# hexa2wide.net
KiCad netlist of a schematic drawn in EAGLE
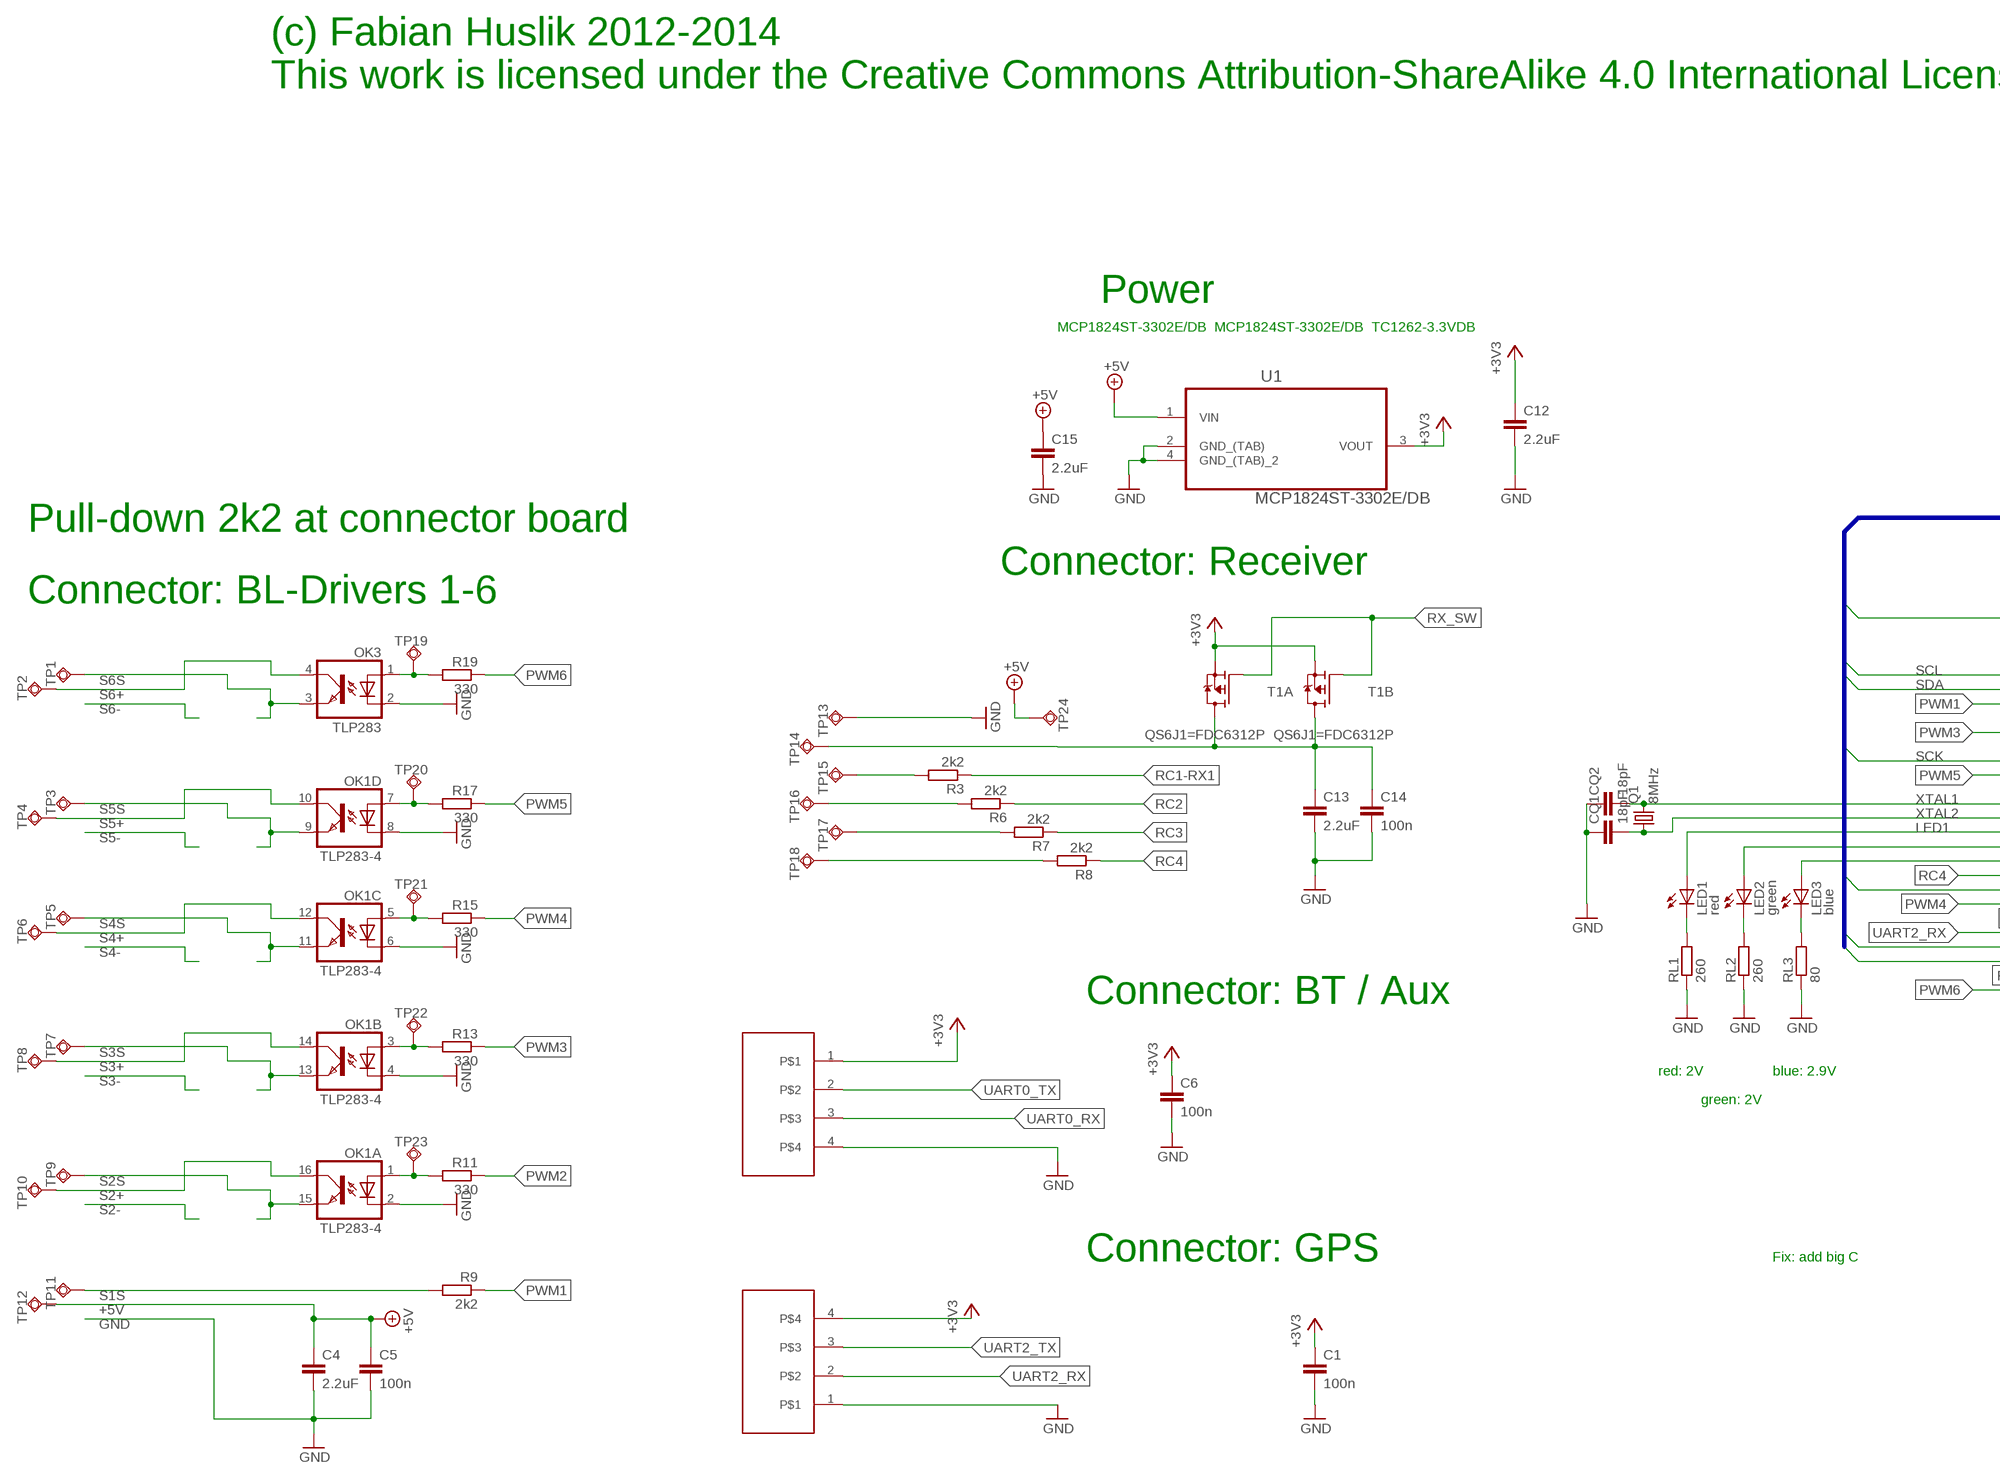
[diagram p0: schematic, sheet 1, part 1 of 2]
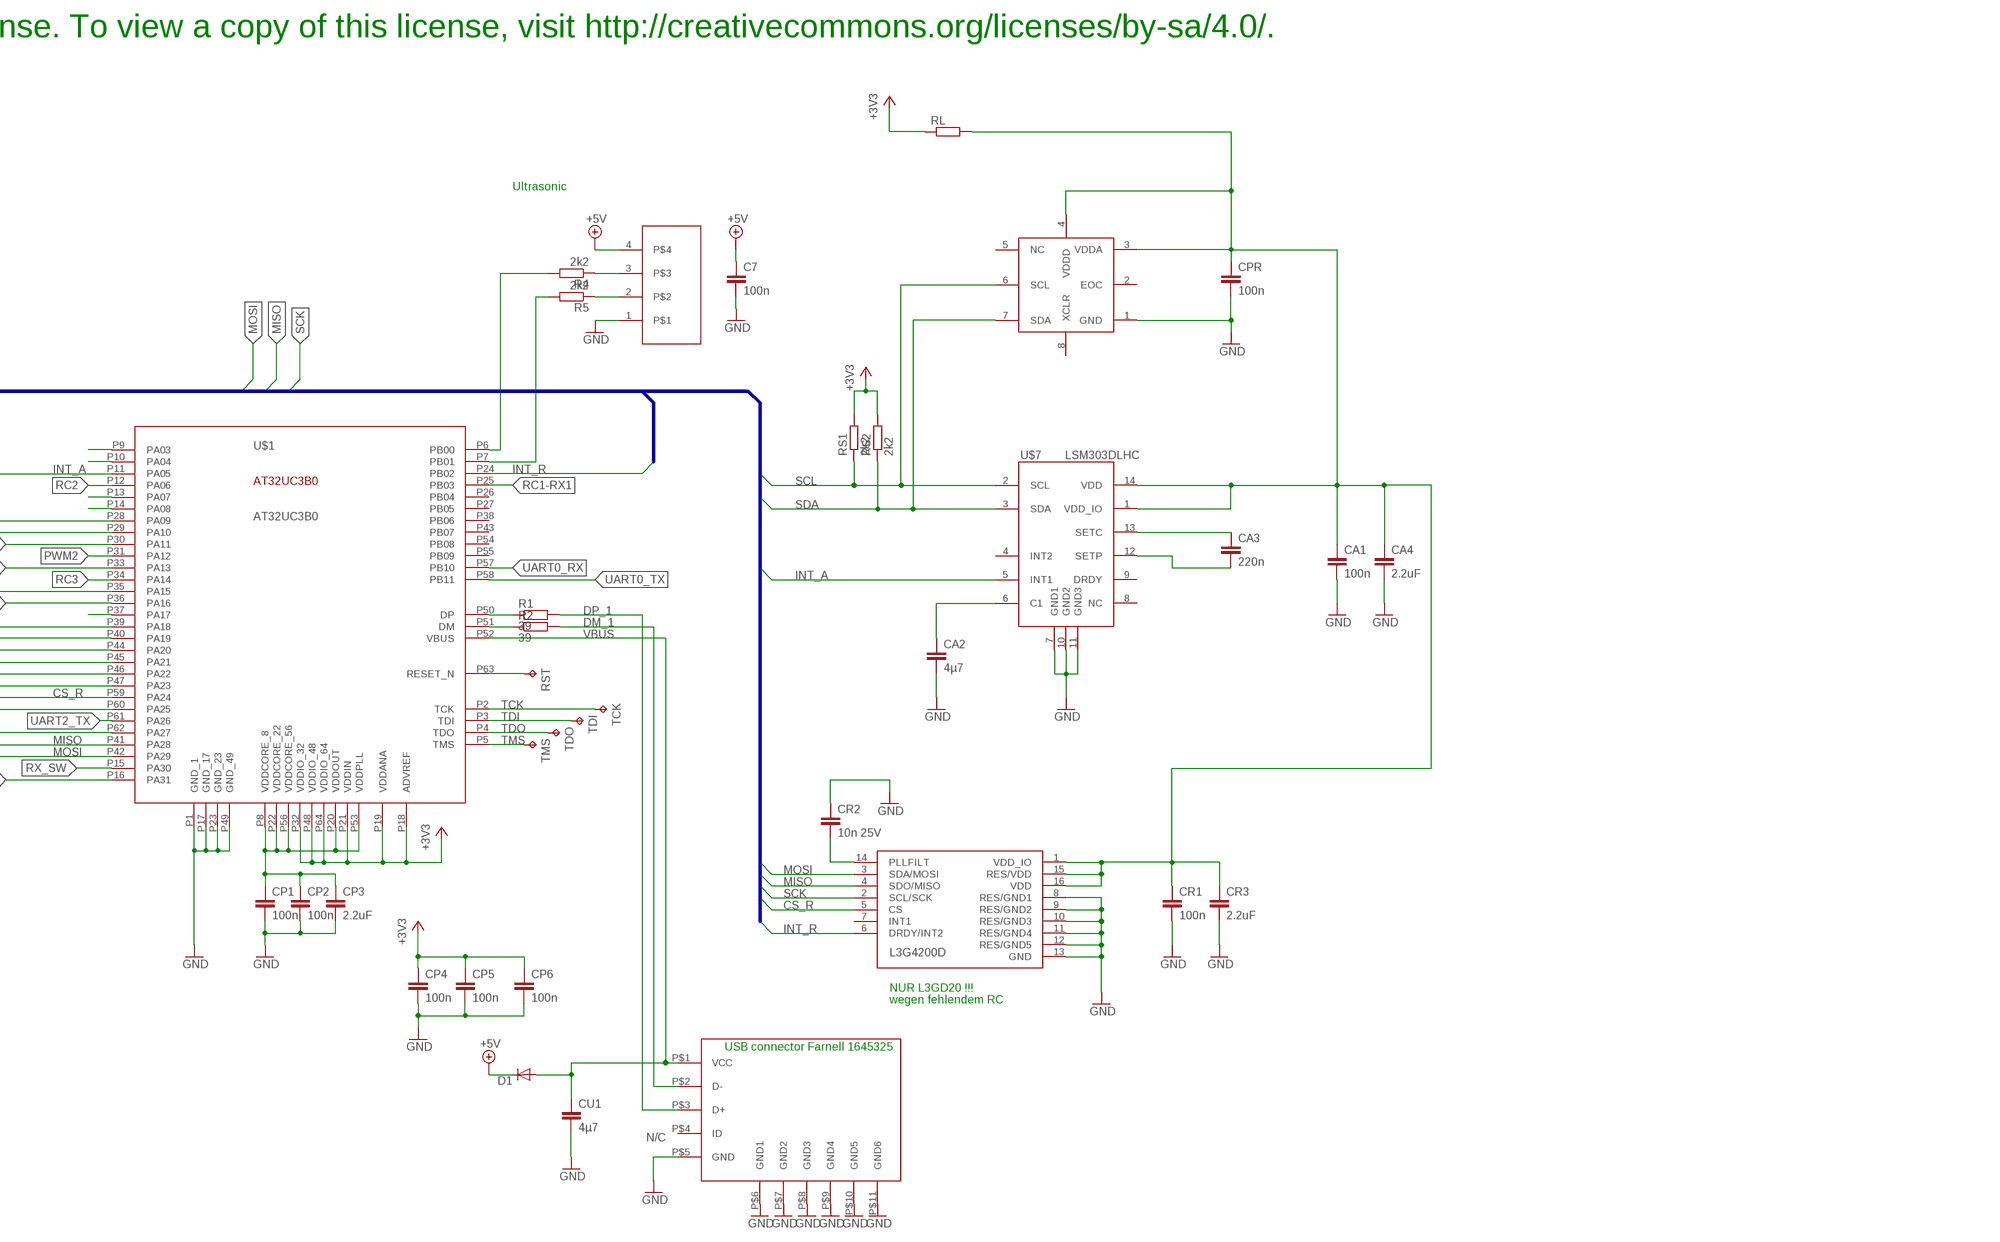
[diagram p1: schematic, sheet 1, part 2 of 2]

(export (version "E")
  (design (tool "Eeschema 10.0.6"))
  (components
    (comp (ref "C1")
      (value "100n")
      (footprint "eagle-import:C0402")
      (fields (field (name "MF") "MULTICOMP") (field (name "MPN") "MCCA000050"))
      (libsource (lib "eagle-import") (part "C-EUC0402"))
    )
    (comp (ref "C4")
      (value "2.2uF")
      (footprint "eagle-import:C0603K")
      (fields (field (name "MF") "MURATA") (field (name "MPN") "GRM188R61C225KE15D"))
      (libsource (lib "eagle-import") (part "C-EUC0603K"))
    )
    (comp (ref "C5")
      (value "100n")
      (footprint "eagle-import:C0402")
      (fields (field (name "MF") "MULTICOMP") (field (name "MPN") "MCCA000050"))
      (libsource (lib "eagle-import") (part "C-EUC0402"))
    )
    (comp (ref "C6")
      (value "100n")
      (footprint "eagle-import:C0402")
      (fields (field (name "MF") "MULTICOMP") (field (name "MPN") "MCCA000050"))
      (libsource (lib "eagle-import") (part "C-EUC0402"))
    )
    (comp (ref "C7")
      (value "100n")
      (footprint "eagle-import:C0402")
      (fields (field (name "MF") "MULTICOMP") (field (name "MPN") "MCCA000050"))
      (libsource (lib "eagle-import") (part "C-EUC0402"))
    )
    (comp (ref "C12")
      (value "2.2uF")
      (footprint "eagle-import:C0603K")
      (fields (field (name "MF") "MURATA") (field (name "MPN") "GRM188R61C225KE15D"))
      (libsource (lib "eagle-import") (part "C-EUC0603K"))
    )
    (comp (ref "C13")
      (value "2.2uF")
      (footprint "eagle-import:C0603K")
      (fields (field (name "MF") "MURATA") (field (name "MPN") "GRM188R61C225KE15D"))
      (libsource (lib "eagle-import") (part "C-EUC0603K"))
    )
    (comp (ref "C14")
      (value "100n")
      (footprint "eagle-import:C0402")
      (fields (field (name "MF") "MULTICOMP") (field (name "MPN") "MCCA000050"))
      (libsource (lib "eagle-import") (part "C-EUC0402"))
    )
    (comp (ref "C15")
      (value "2.2uF")
      (footprint "eagle-import:C0603K")
      (fields (field (name "MF") "MURATA") (field (name "MPN") "GRM188R61C225KE15D"))
      (libsource (lib "eagle-import") (part "C-EUC0603K"))
    )
    (comp (ref "CA1")
      (value "100n")
      (footprint "eagle-import:C0402")
      (fields (field (name "MF") "MULTICOMP") (field (name "MPN") "MCCA000050"))
      (libsource (lib "eagle-import") (part "C-EUC0402"))
    )
    (comp (ref "CA2")
      (value "4µ7")
      (footprint "eagle-import:C0805")
      (fields (field (name "MF") "MURATA") (field (name "MPN") "GRM219R61C475KE15D"))
      (libsource (lib "eagle-import") (part "C-EUC0805"))
    )
    (comp (ref "CA3")
      (value "220n")
      (footprint "eagle-import:C0402")
      (fields (field (name "MF") "KEMET") (field (name "MPN") "C0402C224K9PACTU"))
      (libsource (lib "eagle-import") (part "C-EUC0402"))
    )
    (comp (ref "CA4")
      (value "2.2uF")
      (footprint "eagle-import:C0603K")
      (fields (field (name "MF") "MURATA") (field (name "MPN") "GRM188R61C225KE15D"))
      (libsource (lib "eagle-import") (part "C-EUC0603K"))
    )
    (comp (ref "CP1")
      (value "100n")
      (footprint "eagle-import:C0402")
      (fields (field (name "MF") "MULTICOMP") (field (name "MPN") "MCCA000050"))
      (libsource (lib "eagle-import") (part "C-EUC0402"))
    )
    (comp (ref "CP2")
      (value "100n")
      (footprint "eagle-import:C0402")
      (fields (field (name "MF") "MULTICOMP") (field (name "MPN") "MCCA000050"))
      (libsource (lib "eagle-import") (part "C-EUC0402"))
    )
    (comp (ref "CP3")
      (value "2.2uF")
      (footprint "eagle-import:C0603K")
      (fields (field (name "MF") "MURATA") (field (name "MPN") "GRM188R61C225KE15D"))
      (libsource (lib "eagle-import") (part "C-EUC0603K"))
    )
    (comp (ref "CP4")
      (value "100n")
      (footprint "eagle-import:C0402")
      (fields (field (name "MF") "MULTICOMP") (field (name "MPN") "MCCA000050"))
      (libsource (lib "eagle-import") (part "C-EUC0402"))
    )
    (comp (ref "CP5")
      (value "100n")
      (footprint "eagle-import:C0402")
      (fields (field (name "MF") "MULTICOMP") (field (name "MPN") "MCCA000050"))
      (libsource (lib "eagle-import") (part "C-EUC0402"))
    )
    (comp (ref "CP6")
      (value "100n")
      (footprint "eagle-import:C0402")
      (fields (field (name "MF") "MULTICOMP") (field (name "MPN") "MCCA000050"))
      (libsource (lib "eagle-import") (part "C-EUC0402"))
    )
    (comp (ref "CPR")
      (value "100n")
      (footprint "eagle-import:C0402")
      (fields (field (name "MF") "MULTICOMP") (field (name "MPN") "MCCA000050"))
      (libsource (lib "eagle-import") (part "C-EUC0402"))
    )
    (comp (ref "CQ1")
      (value "18pF")
      (footprint "eagle-import:C0402")
      (fields (field (name "MF") "KEMET") (field (name "MPN") "C0402C180J5GACTU"))
      (libsource (lib "eagle-import") (part "C-EUC0402"))
    )
    (comp (ref "CQ2")
      (value "18pF")
      (footprint "eagle-import:C0402")
      (fields (field (name "MF") "KEMET") (field (name "MPN") "C0402C180J5GACTU"))
      (libsource (lib "eagle-import") (part "C-EUC0402"))
    )
    (comp (ref "CR1")
      (value "100n")
      (footprint "eagle-import:C0402")
      (fields (field (name "MF") "MULTICOMP") (field (name "MPN") "MCCA000050"))
      (libsource (lib "eagle-import") (part "C-EUC0402"))
    )
    (comp (ref "CR2")
      (value "10n 25V")
      (footprint "eagle-import:C0402")
      (fields (field (name "MF") "MULTICOMP") (field (name "MPN") "MCCA000076"))
      (libsource (lib "eagle-import") (part "C-EUC0402"))
    )
    (comp (ref "CR3")
      (value "2.2uF")
      (footprint "eagle-import:C0603K")
      (fields (field (name "MF") "MURATA") (field (name "MPN") "GRM188R61C225KE15D"))
      (libsource (lib "eagle-import") (part "C-EUC0603K"))
    )
    (comp (ref "CU1")
      (value "4µ7")
      (footprint "eagle-import:C0805")
      (fields (field (name "MF") "MURATA") (field (name "MPN") "GRM219R61C475KE15D"))
      (libsource (lib "eagle-import") (part "C-EUC0805"))
    )
    (comp (ref "D1")
      (value "DIODE-MICROMELF-R")
      (footprint "eagle-import:MICROMELF-R")
      (libsource (lib "eagle-import") (part "DIODE-MICROMELF-R"))
    )
    (comp (ref "LED1")
      (value "red")
      (footprint "eagle-import:CHIP-LED0603")
      (fields (field (name "MF") "AVAGO TECHNOLOGIES") (field (name "MPN") "ASMT-RR45-AQ902"))
      (libsource (lib "eagle-import") (part "LEDCHIP-LED0603"))
    )
    (comp (ref "LED2")
      (value "green")
      (footprint "eagle-import:CHIP-LED0603")
      (fields (field (name "MF") "AVAGO TECHNOLOGIES") (field (name "MPN") "ASMT-RF45-AN002"))
      (libsource (lib "eagle-import") (part "LEDCHIP-LED0603"))
    )
    (comp (ref "LED3")
      (value "blue")
      (footprint "eagle-import:CHIP-LED0603")
      (fields (field (name "MF") "ROHM") (field (name "MPN") "SMLE12BC7TT86Q"))
      (libsource (lib "eagle-import") (part "LEDCHIP-LED0603"))
    )
    (comp (ref "OK1")
      (value "TLP283-4")
      (footprint "eagle-import:MINI-FLAT-16")
      (fields
        (field (name "MF") "AVAGO TECHNOLOGIES")
        (field (name "MPN") "ACPL-247-500E")
        (field (name "OC_FARNELL") "1634758")
      )
      (libsource (lib "eagle-import") (part "TLP283-4"))
    )
    (comp (ref "OK3")
      (value "TLP283")
      (footprint "eagle-import:MINI-FLAT-4")
      (fields
        (field (name "MF") "AVAGO TECHNOLOGIES")
        (field (name "MPN") "ACPL-217-500E")
        (field (name "OC_FARNELL") "1602614")
      )
      (libsource (lib "eagle-import") (part "TLP283"))
    )
    (comp (ref "Q1")
      (value "8MHz")
      (footprint "eagle-import:CTS406")
      (fields
        (field (name "MF") "ABRACON")
        (field (name "MPN") "ABMM2-8.000MHZ-E2-T")
        (field (name "OC_FARNELL") "1611803")
      )
      (libsource (lib "eagle-import") (part "CRYSTALCTS406"))
    )
    (comp (ref "R1")
      (value "39")
      (footprint "eagle-import:R0402")
      (fields (field (name "MF") "VISHAY DRALORIC") (field (name "MPN") "CRCW040239R0FKEAHP"))
      (libsource (lib "eagle-import") (part "R-EU_R0402"))
    )
    (comp (ref "R2")
      (value "39")
      (footprint "eagle-import:R0402")
      (fields (field (name "MF") "VISHAY DRALORIC") (field (name "MPN") "CRCW040239R0FKEAHP"))
      (libsource (lib "eagle-import") (part "R-EU_R0402"))
    )
    (comp (ref "R3")
      (value "2k2")
      (footprint "eagle-import:R0402")
      (fields (field (name "MF") "VISHAY DRALORIC") (field (name "MPN") "CRCW040210K5FKED"))
      (libsource (lib "eagle-import") (part "R-EU_R0402"))
    )
    (comp (ref "R4")
      (value "2k2")
      (footprint "eagle-import:R0402")
      (fields (field (name "MF") "VISHAY DRALORIC") (field (name "MPN") "CRCW040210K5FKED"))
      (libsource (lib "eagle-import") (part "R-EU_R0402"))
    )
    (comp (ref "R5")
      (value "2k2")
      (footprint "eagle-import:R0402")
      (fields (field (name "MF") "VISHAY DRALORIC") (field (name "MPN") "CRCW040210K5FKED"))
      (libsource (lib "eagle-import") (part "R-EU_R0402"))
    )
    (comp (ref "R6")
      (value "2k2")
      (footprint "eagle-import:R0402")
      (fields (field (name "MF") "VISHAY DRALORIC") (field (name "MPN") "CRCW040210K5FKED"))
      (libsource (lib "eagle-import") (part "R-EU_R0402"))
    )
    (comp (ref "R7")
      (value "2k2")
      (footprint "eagle-import:R0402")
      (fields (field (name "MF") "VISHAY DRALORIC") (field (name "MPN") "CRCW040210K5FKED"))
      (libsource (lib "eagle-import") (part "R-EU_R0402"))
    )
    (comp (ref "R8")
      (value "2k2")
      (footprint "eagle-import:R0402")
      (fields (field (name "MF") "VISHAY DRALORIC") (field (name "MPN") "CRCW040210K5FKED"))
      (libsource (lib "eagle-import") (part "R-EU_R0402"))
    )
    (comp (ref "R9")
      (value "2k2")
      (footprint "eagle-import:R0402")
      (fields (field (name "MF") "VISHAY DRALORIC") (field (name "MPN") "CRCW040210K5FKED"))
      (libsource (lib "eagle-import") (part "R-EU_R0402"))
    )
    (comp (ref "R11")
      (value "330")
      (footprint "eagle-import:R0402")
      (fields (field (name "MF") "MULTICOMP") (field (name "MPN") "MCMR04X331 JTL"))
      (libsource (lib "eagle-import") (part "R-EU_R0402"))
    )
    (comp (ref "R13")
      (value "330")
      (footprint "eagle-import:R0402")
      (fields (field (name "MF") "MULTICOMP") (field (name "MPN") "MCMR04X331 JTL"))
      (libsource (lib "eagle-import") (part "R-EU_R0402"))
    )
    (comp (ref "R15")
      (value "330")
      (footprint "eagle-import:R0402")
      (fields (field (name "MF") "MULTICOMP") (field (name "MPN") "MCMR04X331 JTL"))
      (libsource (lib "eagle-import") (part "R-EU_R0402"))
    )
    (comp (ref "R17")
      (value "330")
      (footprint "eagle-import:R0402")
      (fields (field (name "MF") "MULTICOMP") (field (name "MPN") "MCMR04X331 JTL"))
      (libsource (lib "eagle-import") (part "R-EU_R0402"))
    )
    (comp (ref "R19")
      (value "330")
      (footprint "eagle-import:R0402")
      (fields (field (name "MF") "MULTICOMP") (field (name "MPN") "MCMR04X331 JTL"))
      (libsource (lib "eagle-import") (part "R-EU_R0402"))
    )
    (comp (ref "RL")
      (value "R-EU_R0603")
      (footprint "eagle-import:R0603")
      (fields (field (name "MF") "WURTH ELEKTRONIK") (field (name "MPN") "74279266"))
      (libsource (lib "eagle-import") (part "R-EU_R0603"))
    )
    (comp (ref "RL1")
      (value "260")
      (footprint "eagle-import:R0402")
      (fields (field (name "MF") "VISHAY DRALORIC") (field (name "MPN") "CRCW0402604RFKED"))
      (libsource (lib "eagle-import") (part "R-EU_R0402"))
    )
    (comp (ref "RL2")
      (value "260")
      (footprint "eagle-import:R0402")
      (fields (field (name "MF") "VISHAY DRALORIC") (field (name "MPN") "CRCW0402604RFKED"))
      (libsource (lib "eagle-import") (part "R-EU_R0402"))
    )
    (comp (ref "RL3")
      (value "80")
      (footprint "eagle-import:R0402")
      (fields (field (name "MF") "PANASONIC") (field (name "MPN") "ERJ2RKF8062X"))
      (libsource (lib "eagle-import") (part "R-EU_R0402"))
    )
    (comp (ref "RS1")
      (value "2k2")
      (footprint "eagle-import:R0402")
      (fields (field (name "MF") "VISHAY DRALORIC") (field (name "MPN") "CRCW040210K5FKED"))
      (libsource (lib "eagle-import") (part "R-EU_R0402"))
    )
    (comp (ref "RS2")
      (value "2k2")
      (footprint "eagle-import:R0402")
      (fields (field (name "MF") "VISHAY DRALORIC") (field (name "MPN") "CRCW040210K5FKED"))
      (libsource (lib "eagle-import") (part "R-EU_R0402"))
    )
    (comp (ref "RST")
      (value "TPB1,27")
      (footprint "eagle-import:B1,27")
      (libsource (lib "eagle-import") (part "TPB1,27"))
    )
    (comp (ref "T1")
      (value "QS6J1=FDC6312P")
      (footprint "eagle-import:SUPERSOT-6")
      (fields
        (field (name "MF") "FAIRCHILD SEMICONDUCTOR")
        (field (name "MPN") "FDC6312P")
        (field (name "OC_FARNELL") "1700713")
      )
      (libsource (lib "eagle-import") (part "QS6J1=FDC6312P"))
    )
    (comp (ref "TCK")
      (value "TPB1,27")
      (footprint "eagle-import:B1,27")
      (libsource (lib "eagle-import") (part "TPB1,27"))
    )
    (comp (ref "TDI")
      (value "TPB1,27")
      (footprint "eagle-import:B1,27")
      (libsource (lib "eagle-import") (part "TPB1,27"))
    )
    (comp (ref "TDO")
      (value "TPB1,27")
      (footprint "eagle-import:B1,27")
      (libsource (lib "eagle-import") (part "TPB1,27"))
    )
    (comp (ref "TMS")
      (value "TPB1,27")
      (footprint "eagle-import:B1,27")
      (libsource (lib "eagle-import") (part "TPB1,27"))
    )
    (comp (ref "TP1")
      (value "TPSQTP16SQ")
      (footprint "eagle-import:TP16SQ")
      (libsource (lib "eagle-import") (part "TPSQTP16SQ"))
    )
    (comp (ref "TP2")
      (value "TPSQTP16SQ")
      (footprint "eagle-import:TP16SQ")
      (libsource (lib "eagle-import") (part "TPSQTP16SQ"))
    )
    (comp (ref "TP3")
      (value "TPSQTP16SQ")
      (footprint "eagle-import:TP16SQ")
      (libsource (lib "eagle-import") (part "TPSQTP16SQ"))
    )
    (comp (ref "TP4")
      (value "TPSQTP16SQ")
      (footprint "eagle-import:TP16SQ")
      (libsource (lib "eagle-import") (part "TPSQTP16SQ"))
    )
    (comp (ref "TP5")
      (value "TPSQTP16SQ")
      (footprint "eagle-import:TP16SQ")
      (libsource (lib "eagle-import") (part "TPSQTP16SQ"))
    )
    (comp (ref "TP6")
      (value "TPSQTP16SQ")
      (footprint "eagle-import:TP16SQ")
      (libsource (lib "eagle-import") (part "TPSQTP16SQ"))
    )
    (comp (ref "TP7")
      (value "TPSQTP16SQ")
      (footprint "eagle-import:TP16SQ")
      (libsource (lib "eagle-import") (part "TPSQTP16SQ"))
    )
    (comp (ref "TP8")
      (value "TPSQTP16SQ")
      (footprint "eagle-import:TP16SQ")
      (libsource (lib "eagle-import") (part "TPSQTP16SQ"))
    )
    (comp (ref "TP9")
      (value "TPSQTP16SQ")
      (footprint "eagle-import:TP16SQ")
      (libsource (lib "eagle-import") (part "TPSQTP16SQ"))
    )
    (comp (ref "TP10")
      (value "TPSQTP16SQ")
      (footprint "eagle-import:TP16SQ")
      (libsource (lib "eagle-import") (part "TPSQTP16SQ"))
    )
    (comp (ref "TP11")
      (value "TPSQTP16SQ")
      (footprint "eagle-import:TP16SQ")
      (libsource (lib "eagle-import") (part "TPSQTP16SQ"))
    )
    (comp (ref "TP12")
      (value "TPSQTP16SQ")
      (footprint "eagle-import:TP16SQ")
      (libsource (lib "eagle-import") (part "TPSQTP16SQ"))
    )
    (comp (ref "TP13")
      (value "TPSQTP16SQ")
      (footprint "eagle-import:TP16SQ")
      (libsource (lib "eagle-import") (part "TPSQTP16SQ"))
    )
    (comp (ref "TP14")
      (value "TPSQTP16SQ")
      (footprint "eagle-import:TP16SQ")
      (libsource (lib "eagle-import") (part "TPSQTP16SQ"))
    )
    (comp (ref "TP15")
      (value "TPSQTP16SQ")
      (footprint "eagle-import:TP16SQ")
      (libsource (lib "eagle-import") (part "TPSQTP16SQ"))
    )
    (comp (ref "TP16")
      (value "TPSQTP16SQ")
      (footprint "eagle-import:TP16SQ")
      (libsource (lib "eagle-import") (part "TPSQTP16SQ"))
    )
    (comp (ref "TP17")
      (value "TPSQTP16SQ")
      (footprint "eagle-import:TP16SQ")
      (libsource (lib "eagle-import") (part "TPSQTP16SQ"))
    )
    (comp (ref "TP18")
      (value "TPSQTP16SQ")
      (footprint "eagle-import:TP16SQ")
      (libsource (lib "eagle-import") (part "TPSQTP16SQ"))
    )
    (comp (ref "TP19")
      (value "TPSQTP10SQ")
      (footprint "eagle-import:TP10SQ")
      (libsource (lib "eagle-import") (part "TPSQTP10SQ"))
    )
    (comp (ref "TP20")
      (value "TPSQTP10SQ")
      (footprint "eagle-import:TP10SQ")
      (libsource (lib "eagle-import") (part "TPSQTP10SQ"))
    )
    (comp (ref "TP21")
      (value "TPSQTP10SQ")
      (footprint "eagle-import:TP10SQ")
      (libsource (lib "eagle-import") (part "TPSQTP10SQ"))
    )
    (comp (ref "TP22")
      (value "TPSQTP10SQ")
      (footprint "eagle-import:TP10SQ")
      (libsource (lib "eagle-import") (part "TPSQTP10SQ"))
    )
    (comp (ref "TP23")
      (value "TPSQTP10SQ")
      (footprint "eagle-import:TP10SQ")
      (libsource (lib "eagle-import") (part "TPSQTP10SQ"))
    )
    (comp (ref "TP24")
      (value "TPSQTP10SQ")
      (footprint "eagle-import:TP10SQ")
      (libsource (lib "eagle-import") (part "TPSQTP10SQ"))
    )
    (comp (ref "U$1")
      (value "AT32UC3B0")
      (footprint "eagle-import:JEDEC_MS-026")
      (fields (field (name "MF") "ATMEL") (field (name "MPN") "AT32UC3B0256-A2UT"))
      (libsource (lib "eagle-import") (part "AT32UC3B0"))
    )
    (comp (ref "U$4")
      (value "UBB_MICRO_HIROSE")
      (footprint "eagle-import:USB_MICRO")
      (fields (field (name "MF") "HRS (HIROSE)") (field (name "MPN") "ZX62-B-5PA(11)"))
      (libsource (lib "eagle-import") (part "UBB_MICRO_HIROSE"))
    )
    (comp (ref "U$5")
      (value "L3G4200DHAND")
      (footprint "eagle-import:LGA16_HAND")
      (fields (field (name "MF") "STMICROELECTRONICS") (field (name "MPN") "L3GD20"))
      (libsource (lib "eagle-import") (part "L3G4200DHAND"))
    )
    (comp (ref "U$7")
      (value "LSM303HAND")
      (footprint "eagle-import:LGA14_HAND")
      (fields (field (name "MF") "STMICROELECTRONICS") (field (name "MPN") "LSM303DLHC"))
      (libsource (lib "eagle-import") (part "LSM303HAND"))
    )
    (comp (ref "U$9")
      (value "BMP085")
      (footprint "eagle-import:BMP085")
      (libsource (lib "eagle-import") (part "BMP085"))
    )
    (comp (ref "U$10")
      (value "4WIRE_CONN")
      (footprint "eagle-import:4WIRE_PIN")
      (libsource (lib "eagle-import") (part "4WIRE_CONN"))
    )
    (comp (ref "U$11")
      (value "4WIRE_CONN")
      (footprint "eagle-import:4WIRE_PIN")
      (libsource (lib "eagle-import") (part "4WIRE_CONN"))
    )
    (comp (ref "U$12")
      (value "4WIRE_CONN")
      (footprint "eagle-import:4WIRE_PIN")
      (libsource (lib "eagle-import") (part "4WIRE_CONN"))
    )
    (comp (ref "U1")
      (value "MCP1824ST-3302E/DB")
      (footprint "eagle-import:SOT230P700X180-4N")
      (fields
        (field (name "MF") "MICROCHIP")
        (field (name "MPN") "MCP1824ST-3302E/DB")
        (field (name "OC_FARNELL") "1578379")
      )
      (libsource (lib "eagle-import") (part "MCP1824ST-3302E/DB"))
    )
  )
  (nets
    (net (code "1") (name "+3V3") (class "Default")
      (node (ref "C1") (pin "1") (pinfunction "1_1") (pintype "passive"))
      (node (ref "C12") (pin "1") (pinfunction "1_1") (pintype "passive"))
      (node (ref "C6") (pin "1") (pinfunction "1_1") (pintype "passive"))
      (node (ref "CP4") (pin "1") (pinfunction "1_1") (pintype "passive"))
      (node (ref "CP5") (pin "1") (pinfunction "1_1") (pintype "passive"))
      (node (ref "CP6") (pin "1") (pinfunction "1_1") (pintype "passive"))
      (node (ref "RL") (pin "1") (pinfunction "1_1") (pintype "passive"))
      (node (ref "RS1") (pin "2") (pinfunction "2_2") (pintype "passive"))
      (node (ref "RS2") (pin "2") (pinfunction "2_2") (pintype "passive"))
      (node (ref "T1") (pin "P$2") (pinfunction "S_P$2") (pintype "passive"))
      (node (ref "T1") (pin "P$5") (pinfunction "S_P$5") (pintype "passive"))
      (node (ref "U$1") (pin "P18") (pinfunction "ADVREF_P18") (pintype "power_in"))
      (node (ref "U$1") (pin "P19") (pinfunction "VDDANA_P19") (pintype "power_in"))
      (node (ref "U$1") (pin "P21") (pinfunction "VDDIN_P21") (pintype "power_in"))
      (node (ref "U$1") (pin "P32") (pinfunction "VDDIO_32_P32") (pintype "power_in"))
      (node (ref "U$1") (pin "P48") (pinfunction "VDDIO_48_P48") (pintype "power_in"))
      (node (ref "U$1") (pin "P64") (pinfunction "VDDIO_64_P64") (pintype "power_in"))
      (node (ref "U$10") (pin "4") (pinfunction "P$4_4") (pintype "bidirectional"))
      (node (ref "U$11") (pin "1") (pinfunction "P$1_1") (pintype "bidirectional"))
      (node (ref "U1") (pin "3") (pinfunction "VOUT_3") (pintype "output"))
    )
    (net (code "2") (name "+5V") (class "Default")
      (node (ref "C15") (pin "1") (pinfunction "1_1") (pintype "passive"))
      (node (ref "C4") (pin "1") (pinfunction "1_1") (pintype "passive"))
      (node (ref "C5") (pin "1") (pinfunction "1_1") (pintype "passive"))
      (node (ref "C7") (pin "1") (pinfunction "1_1") (pintype "passive"))
      (node (ref "D1") (pin "C") (pinfunction "C_C") (pintype "passive"))
      (node (ref "TP12") (pin "TP") (pinfunction "TP_TP") (pintype "input"))
      (node (ref "TP24") (pin "TP") (pinfunction "TP_TP") (pintype "input"))
      (node (ref "U$12") (pin "4") (pinfunction "P$4_4") (pintype "bidirectional"))
      (node (ref "U1") (pin "1") (pinfunction "VIN_1") (pintype "input"))
    )
    (net (code "3") (name "/CS_R") (class "Default")
      (node (ref "U$1") (pin "P59") (pinfunction "PA24_P59") (pintype "bidirectional"))
      (node (ref "U$5") (pin "5") (pinfunction "CS_5") (pintype "input"))
    )
    (net (code "4") (name "/DM_1") (class "Default")
      (node (ref "R2") (pin "2") (pinfunction "2_2") (pintype "passive"))
      (node (ref "U$4") (pin "P$2") (pinfunction "D-_P$2") (pintype "bidirectional"))
    )
    (net (code "5") (name "/DP_1") (class "Default")
      (node (ref "R1") (pin "2") (pinfunction "2_2") (pintype "passive"))
      (node (ref "U$4") (pin "P$3") (pinfunction "D+_P$3") (pintype "bidirectional"))
    )
    (net (code "6") (name "/INT_A") (class "Default")
      (node (ref "U$1") (pin "P11") (pinfunction "PA05_P11") (pintype "bidirectional"))
      (node (ref "U$7") (pin "5") (pinfunction "INT1_5") (pintype "bidirectional"))
    )
    (net (code "7") (name "/INT_R") (class "Default")
      (node (ref "U$1") (pin "P24") (pinfunction "PB02_P24") (pintype "bidirectional"))
      (node (ref "U$5") (pin "6") (pinfunction "DRDY/INT2_6") (pintype "output"))
    )
    (net (code "8") (name "/LED1") (class "Default")
      (node (ref "LED1") (pin "A") (pinfunction "A_A") (pintype "passive"))
      (node (ref "U$1") (pin "P44") (pinfunction "PA20_P44") (pintype "bidirectional"))
    )
    (net (code "9") (name "/S1S") (class "Default")
      (node (ref "R9") (pin "2") (pinfunction "2_2") (pintype "passive"))
      (node (ref "TP11") (pin "TP") (pinfunction "TP_TP") (pintype "input"))
    )
    (net (code "10") (name "/S2+") (class "Default")
      (node (ref "OK1") (pin "16") (pinfunction "COL_16") (pintype "passive"))
      (node (ref "TP10") (pin "TP") (pinfunction "TP_TP") (pintype "input"))
    )
    (net (code "12") (name "/S2S") (class "Default")
      (node (ref "OK1") (pin "15") (pinfunction "EMIT_15") (pintype "passive"))
      (node (ref "TP9") (pin "TP") (pinfunction "TP_TP") (pintype "input"))
    )
    (net (code "13") (name "/S3+") (class "Default")
      (node (ref "OK1") (pin "14") (pinfunction "COL_14") (pintype "passive"))
      (node (ref "TP8") (pin "TP") (pinfunction "TP_TP") (pintype "input"))
    )
    (net (code "15") (name "/S3S") (class "Default")
      (node (ref "OK1") (pin "13") (pinfunction "EMIT_13") (pintype "passive"))
      (node (ref "TP7") (pin "TP") (pinfunction "TP_TP") (pintype "input"))
    )
    (net (code "16") (name "/S4+") (class "Default")
      (node (ref "OK1") (pin "12") (pinfunction "COL_12") (pintype "passive"))
      (node (ref "TP6") (pin "TP") (pinfunction "TP_TP") (pintype "input"))
    )
    (net (code "18") (name "/S4S") (class "Default")
      (node (ref "OK1") (pin "11") (pinfunction "EMIT_11") (pintype "passive"))
      (node (ref "TP5") (pin "TP") (pinfunction "TP_TP") (pintype "input"))
    )
    (net (code "19") (name "/S5+") (class "Default")
      (node (ref "OK1") (pin "10") (pinfunction "COL_10") (pintype "passive"))
      (node (ref "TP4") (pin "TP") (pinfunction "TP_TP") (pintype "input"))
    )
    (net (code "21") (name "/S5S") (class "Default")
      (node (ref "OK1") (pin "9") (pinfunction "EMIT_9") (pintype "passive"))
      (node (ref "TP3") (pin "TP") (pinfunction "TP_TP") (pintype "input"))
    )
    (net (code "22") (name "/S6+") (class "Default")
      (node (ref "OK3") (pin "4") (pinfunction "COL_4") (pintype "passive"))
      (node (ref "TP2") (pin "TP") (pinfunction "TP_TP") (pintype "input"))
    )
    (net (code "24") (name "/S6S") (class "Default")
      (node (ref "OK3") (pin "3") (pinfunction "EMIT_3") (pintype "passive"))
      (node (ref "TP1") (pin "TP") (pinfunction "TP_TP") (pintype "input"))
    )
    (net (code "25") (name "/SCL") (class "Default")
      (node (ref "RS1") (pin "1") (pinfunction "1_1") (pintype "passive"))
      (node (ref "U$1") (pin "P28") (pinfunction "PA09_P28") (pintype "bidirectional"))
      (node (ref "U$7") (pin "2") (pinfunction "SCL_2") (pintype "bidirectional"))
      (node (ref "U$9") (pin "6") (pinfunction "SCL_6") (pintype "bidirectional"))
    )
    (net (code "26") (name "/SDA") (class "Default")
      (node (ref "RS2") (pin "1") (pinfunction "1_1") (pintype "passive"))
      (node (ref "U$1") (pin "P29") (pinfunction "PA10_P29") (pintype "bidirectional"))
      (node (ref "U$7") (pin "3") (pinfunction "SDA_3") (pintype "bidirectional"))
      (node (ref "U$9") (pin "7") (pinfunction "SDA_7") (pintype "bidirectional"))
    )
    (net (code "27") (name "/TCK") (class "Default")
      (node (ref "TCK") (pin "TP") (pinfunction "TP_TP") (pintype "input"))
      (node (ref "U$1") (pin "P2") (pinfunction "TCK_P2") (pintype "input"))
    )
    (net (code "28") (name "/TDI") (class "Default")
      (node (ref "TDI") (pin "TP") (pinfunction "TP_TP") (pintype "input"))
      (node (ref "U$1") (pin "P3") (pinfunction "TDI_P3") (pintype "input"))
    )
    (net (code "29") (name "/TDO") (class "Default")
      (node (ref "TDO") (pin "TP") (pinfunction "TP_TP") (pintype "input"))
      (node (ref "U$1") (pin "P4") (pinfunction "TDO_P4") (pintype "output"))
    )
    (net (code "30") (name "/TMS") (class "Default")
      (node (ref "TMS") (pin "TP") (pinfunction "TP_TP") (pintype "input"))
      (node (ref "U$1") (pin "P5") (pinfunction "TMS_P5") (pintype "input"))
    )
    (net (code "31") (name "/VBUS") (class "Default")
      (node (ref "CU1") (pin "1") (pinfunction "1_1") (pintype "passive"))
      (node (ref "D1") (pin "A") (pinfunction "A_A") (pintype "passive"))
      (node (ref "U$1") (pin "P52") (pinfunction "VBUS_P52") (pintype "power_in"))
      (node (ref "U$4") (pin "P$1") (pinfunction "VCC_P$1") (pintype "bidirectional"))
    )
    (net (code "32") (name "/XTAL1") (class "Default")
      (node (ref "CQ2") (pin "2") (pinfunction "2_2") (pintype "passive"))
      (node (ref "Q1") (pin "3") (pinfunction "2_3") (pintype "passive"))
      (node (ref "U$1") (pin "P39") (pinfunction "PA18_P39") (pintype "bidirectional"))
    )
    (net (code "33") (name "/XTAL2") (class "Default")
      (node (ref "CQ1") (pin "2") (pinfunction "2_2") (pintype "passive"))
      (node (ref "Q1") (pin "1") (pinfunction "1_1") (pintype "passive"))
      (node (ref "U$1") (pin "P40") (pinfunction "PA19_P40") (pintype "bidirectional"))
    )
    (net (code "34") (name "GND") (class "Default")
      (node (ref "C1") (pin "2") (pinfunction "2_2") (pintype "passive"))
      (node (ref "C12") (pin "2") (pinfunction "2_2") (pintype "passive"))
      (node (ref "C13") (pin "2") (pinfunction "2_2") (pintype "passive"))
      (node (ref "C14") (pin "2") (pinfunction "2_2") (pintype "passive"))
      (node (ref "C15") (pin "2") (pinfunction "2_2") (pintype "passive"))
      (node (ref "C4") (pin "2") (pinfunction "2_2") (pintype "passive"))
      (node (ref "C5") (pin "2") (pinfunction "2_2") (pintype "passive"))
      (node (ref "C6") (pin "2") (pinfunction "2_2") (pintype "passive"))
      (node (ref "C7") (pin "2") (pinfunction "2_2") (pintype "passive"))
      (node (ref "CA1") (pin "2") (pinfunction "2_2") (pintype "passive"))
      (node (ref "CA2") (pin "2") (pinfunction "2_2") (pintype "passive"))
      (node (ref "CA4") (pin "2") (pinfunction "2_2") (pintype "passive"))
      (node (ref "CP1") (pin "2") (pinfunction "2_2") (pintype "passive"))
      (node (ref "CP2") (pin "2") (pinfunction "2_2") (pintype "passive"))
      (node (ref "CP3") (pin "2") (pinfunction "2_2") (pintype "passive"))
      (node (ref "CP4") (pin "2") (pinfunction "2_2") (pintype "passive"))
      (node (ref "CP5") (pin "2") (pinfunction "2_2") (pintype "passive"))
      (node (ref "CP6") (pin "2") (pinfunction "2_2") (pintype "passive"))
      (node (ref "CPR") (pin "2") (pinfunction "2_2") (pintype "passive"))
      (node (ref "CQ1") (pin "1") (pinfunction "1_1") (pintype "passive"))
      (node (ref "CQ2") (pin "1") (pinfunction "1_1") (pintype "passive"))
      (node (ref "CR1") (pin "2") (pinfunction "2_2") (pintype "passive"))
      (node (ref "CR2") (pin "1") (pinfunction "1_1") (pintype "passive"))
      (node (ref "CR3") (pin "2") (pinfunction "2_2") (pintype "passive"))
      (node (ref "CU1") (pin "2") (pinfunction "2_2") (pintype "passive"))
      (node (ref "OK1") (pin "2") (pinfunction "C_2") (pintype "passive"))
      (node (ref "OK1") (pin "4") (pinfunction "C_4") (pintype "passive"))
      (node (ref "OK1") (pin "6") (pinfunction "C_6") (pintype "passive"))
      (node (ref "OK1") (pin "8") (pinfunction "C_8") (pintype "passive"))
      (node (ref "OK3") (pin "2") (pinfunction "C_2") (pintype "passive"))
      (node (ref "RL1") (pin "1") (pinfunction "1_1") (pintype "passive"))
      (node (ref "RL2") (pin "1") (pinfunction "1_1") (pintype "passive"))
      (node (ref "RL3") (pin "1") (pinfunction "1_1") (pintype "passive"))
      (node (ref "TP13") (pin "TP") (pinfunction "TP_TP") (pintype "input"))
      (node (ref "U$1") (pin "P1") (pinfunction "GND_1_P1") (pintype "power_in"))
      (node (ref "U$1") (pin "P17") (pinfunction "GND_17_P17") (pintype "power_in"))
      (node (ref "U$1") (pin "P23") (pinfunction "GND_23_P23") (pintype "power_in"))
      (node (ref "U$1") (pin "P49") (pinfunction "GND_49_P49") (pintype "power_in"))
      (node (ref "U$10") (pin "1") (pinfunction "P$1_1") (pintype "bidirectional"))
      (node (ref "U$11") (pin "4") (pinfunction "P$4_4") (pintype "bidirectional"))
      (node (ref "U$12") (pin "1") (pinfunction "P$1_1") (pintype "bidirectional"))
      (node (ref "U$4") (pin "P$10") (pinfunction "GND5_P$10") (pintype "bidirectional"))
      (node (ref "U$4") (pin "P$11") (pinfunction "GND6_P$11") (pintype "bidirectional"))
      (node (ref "U$4") (pin "P$5") (pinfunction "GND_P$5") (pintype "bidirectional"))
      (node (ref "U$4") (pin "P$6") (pinfunction "GND1_P$6") (pintype "bidirectional"))
      (node (ref "U$4") (pin "P$7") (pinfunction "GND2_P$7") (pintype "bidirectional"))
      (node (ref "U$4") (pin "P$8") (pinfunction "GND3_P$8") (pintype "bidirectional"))
      (node (ref "U$4") (pin "P$9") (pinfunction "GND4_P$9") (pintype "bidirectional"))
      (node (ref "U$5") (pin "10") (pinfunction "RES/GND3_10") (pintype "power_in"))
      (node (ref "U$5") (pin "11") (pinfunction "RES/GND4_11") (pintype "power_in"))
      (node (ref "U$5") (pin "12") (pinfunction "RES/GND5_12") (pintype "power_in"))
      (node (ref "U$5") (pin "13") (pinfunction "GND_13") (pintype "power_in"))
      (node (ref "U$5") (pin "8") (pinfunction "RES/GND1_8") (pintype "power_in"))
      (node (ref "U$5") (pin "9") (pinfunction "RES/GND2_9") (pintype "power_in"))
      (node (ref "U$7") (pin "10") (pinfunction "GND2_10") (pintype "bidirectional"))
      (node (ref "U$7") (pin "11") (pinfunction "GND3_11") (pintype "bidirectional"))
      (node (ref "U$7") (pin "7") (pinfunction "GND1_7") (pintype "bidirectional"))
      (node (ref "U$9") (pin "1") (pinfunction "GND_1") (pintype "bidirectional"))
      (node (ref "U1") (pin "2") (pinfunction "GND_(TAB)_2") (pintype "passive"))
      (node (ref "U1") (pin "4") (pinfunction "GND_(TAB)_2_4") (pintype "passive"))
    )
    (net (code "35") (name "MISO") (class "Default")
      (node (ref "U$1") (pin "P41") (pinfunction "PA28_P41") (pintype "bidirectional"))
      (node (ref "U$5") (pin "4") (pinfunction "SDO/MISO_4") (pintype "input"))
    )
    (net (code "36") (name "MOSI") (class "Default")
      (node (ref "U$1") (pin "P42") (pinfunction "PA29_P42") (pintype "bidirectional"))
      (node (ref "U$5") (pin "3") (pinfunction "SDA/MOSI_3") (pintype "bidirectional"))
    )
    (net (code "37") (name "Net-(LED1-PadC)") (class "Default")
      (node (ref "LED1") (pin "C") (pinfunction "C_C") (pintype "passive"))
      (node (ref "RL1") (pin "2") (pinfunction "2_2") (pintype "passive"))
    )
    (net (code "38") (name "Net-(LED2-PadC)") (class "Default")
      (node (ref "LED2") (pin "C") (pinfunction "C_C") (pintype "passive"))
      (node (ref "RL2") (pin "2") (pinfunction "2_2") (pintype "passive"))
    )
    (net (code "39") (name "Net-(LED3-PadC)") (class "Default")
      (node (ref "LED3") (pin "C") (pinfunction "C_C") (pintype "passive"))
      (node (ref "RL3") (pin "2") (pinfunction "2_2") (pintype "passive"))
    )
    (net (code "40") (name "Net-(OK1A-A)") (class "Default")
      (node (ref "OK1") (pin "1") (pinfunction "A_1") (pintype "passive"))
      (node (ref "R11") (pin "2") (pinfunction "2_2") (pintype "passive"))
      (node (ref "TP23") (pin "TP") (pinfunction "TP_TP") (pintype "input"))
    )
    (net (code "41") (name "Net-(OK1B-A)") (class "Default")
      (node (ref "OK1") (pin "3") (pinfunction "A_3") (pintype "passive"))
      (node (ref "R13") (pin "2") (pinfunction "2_2") (pintype "passive"))
      (node (ref "TP22") (pin "TP") (pinfunction "TP_TP") (pintype "input"))
    )
    (net (code "42") (name "Net-(OK1C-A)") (class "Default")
      (node (ref "OK1") (pin "5") (pinfunction "A_5") (pintype "passive"))
      (node (ref "R15") (pin "2") (pinfunction "2_2") (pintype "passive"))
      (node (ref "TP21") (pin "TP") (pinfunction "TP_TP") (pintype "input"))
    )
    (net (code "43") (name "Net-(OK1D-A)") (class "Default")
      (node (ref "OK1") (pin "7") (pinfunction "A_7") (pintype "passive"))
      (node (ref "R17") (pin "2") (pinfunction "2_2") (pintype "passive"))
      (node (ref "TP20") (pin "TP") (pinfunction "TP_TP") (pintype "input"))
    )
    (net (code "44") (name "Net-(OK3-A)") (class "Default")
      (node (ref "OK3") (pin "1") (pinfunction "A_1") (pintype "passive"))
      (node (ref "R19") (pin "2") (pinfunction "2_2") (pintype "passive"))
      (node (ref "TP19") (pin "TP") (pinfunction "TP_TP") (pintype "input"))
    )
    (net (code "45") (name "Net-(R3-Pad2)") (class "Default")
      (node (ref "R3") (pin "2") (pinfunction "2_2") (pintype "passive"))
      (node (ref "TP15") (pin "TP") (pinfunction "TP_TP") (pintype "input"))
    )
    (net (code "46") (name "Net-(R6-Pad2)") (class "Default")
      (node (ref "R6") (pin "2") (pinfunction "2_2") (pintype "passive"))
      (node (ref "TP16") (pin "TP") (pinfunction "TP_TP") (pintype "input"))
    )
    (net (code "47") (name "Net-(R7-Pad2)") (class "Default")
      (node (ref "R7") (pin "2") (pinfunction "2_2") (pintype "passive"))
      (node (ref "TP17") (pin "TP") (pinfunction "TP_TP") (pintype "input"))
    )
    (net (code "48") (name "Net-(R8-Pad2)") (class "Default")
      (node (ref "R8") (pin "2") (pinfunction "2_2") (pintype "passive"))
      (node (ref "TP18") (pin "TP") (pinfunction "TP_TP") (pintype "input"))
    )
    (net (code "49") (name "Net-(T1A-D)") (class "Default")
      (node (ref "C13") (pin "1") (pinfunction "1_1") (pintype "passive"))
      (node (ref "C14") (pin "1") (pinfunction "1_1") (pintype "passive"))
      (node (ref "T1") (pin "P$4") (pinfunction "D_P$4") (pintype "passive"))
      (node (ref "T1") (pin "P$6") (pinfunction "D_P$6") (pintype "passive"))
      (node (ref "TP14") (pin "TP") (pinfunction "TP_TP") (pintype "input"))
    )
    (net (code "50") (name "Net-(U$1-DM)") (class "Default")
      (node (ref "R2") (pin "1") (pinfunction "1_1") (pintype "passive"))
      (node (ref "U$1") (pin "P51") (pinfunction "DM_P51") (pintype "bidirectional"))
    )
    (net (code "51") (name "Net-(U$1-DP)") (class "Default")
      (node (ref "R1") (pin "1") (pinfunction "1_1") (pintype "passive"))
      (node (ref "U$1") (pin "P50") (pinfunction "DP_P50") (pintype "bidirectional"))
    )
    (net (code "52") (name "Net-(U$1-PA21)") (class "Default")
      (node (ref "LED2") (pin "A") (pinfunction "A_A") (pintype "passive"))
      (node (ref "U$1") (pin "P45") (pinfunction "PA21_P45") (pintype "bidirectional"))
    )
    (net (code "53") (name "Net-(U$1-PA22)") (class "Default")
      (node (ref "LED3") (pin "A") (pinfunction "A_A") (pintype "passive"))
      (node (ref "U$1") (pin "P46") (pinfunction "PA22_P46") (pintype "bidirectional"))
    )
    (net (code "54") (name "Net-(U$1-PB00)") (class "Default")
      (node (ref "R4") (pin "2") (pinfunction "2_2") (pintype "passive"))
      (node (ref "U$1") (pin "P6") (pinfunction "PB00_P6") (pintype "bidirectional"))
    )
    (net (code "55") (name "Net-(U$1-PB01)") (class "Default")
      (node (ref "R5") (pin "2") (pinfunction "2_2") (pintype "passive"))
      (node (ref "U$1") (pin "P7") (pinfunction "PB01_P7") (pintype "bidirectional"))
    )
    (net (code "56") (name "Net-(U$1-RESET_N)") (class "Default")
      (node (ref "RST") (pin "TP") (pinfunction "TP_TP") (pintype "input"))
      (node (ref "U$1") (pin "P63") (pinfunction "RESET_N_P63") (pintype "input"))
    )
    (net (code "57") (name "Net-(U$1-VDDCORE_22)") (class "Default")
      (node (ref "CP1") (pin "1") (pinfunction "1_1") (pintype "passive"))
      (node (ref "CP2") (pin "1") (pinfunction "1_1") (pintype "passive"))
      (node (ref "CP3") (pin "1") (pinfunction "1_1") (pintype "passive"))
      (node (ref "U$1") (pin "P20") (pinfunction "VDDOUT_P20") (pintype "power_in"))
      (node (ref "U$1") (pin "P22") (pinfunction "VDDCORE_22_P22") (pintype "power_in"))
      (node (ref "U$1") (pin "P53") (pinfunction "VDDPLL_P53") (pintype "power_in"))
      (node (ref "U$1") (pin "P56") (pinfunction "VDDCORE_56_P56") (pintype "power_in"))
      (node (ref "U$1") (pin "P8") (pinfunction "VDDCORE_8_P8") (pintype "power_in"))
    )
    (net (code "58") (name "Net-(U$5-PLLFILT)") (class "Default")
      (node (ref "CR2") (pin "2") (pinfunction "2_2") (pintype "passive"))
      (node (ref "U$5") (pin "14") (pinfunction "PLLFILT_14") (pintype "bidirectional"))
    )
    (net (code "59") (name "Net-(U$5-RES{slash}VDD)") (class "Default")
      (node (ref "CA1") (pin "1") (pinfunction "1_1") (pintype "passive"))
      (node (ref "CA4") (pin "1") (pinfunction "1_1") (pintype "passive"))
      (node (ref "CPR") (pin "1") (pinfunction "1_1") (pintype "passive"))
      (node (ref "CR1") (pin "1") (pinfunction "1_1") (pintype "passive"))
      (node (ref "CR3") (pin "1") (pinfunction "1_1") (pintype "passive"))
      (node (ref "RL") (pin "2") (pinfunction "2_2") (pintype "passive"))
      (node (ref "U$5") (pin "1") (pinfunction "VDD_IO_1") (pintype "power_in"))
      (node (ref "U$5") (pin "15") (pinfunction "RES/VDD_15") (pintype "power_in"))
      (node (ref "U$5") (pin "16") (pinfunction "VDD_16") (pintype "power_in"))
      (node (ref "U$7") (pin "1") (pinfunction "VDD_IO_1") (pintype "bidirectional"))
      (node (ref "U$7") (pin "14") (pinfunction "VDD_14") (pintype "bidirectional"))
      (node (ref "U$9") (pin "3") (pinfunction "VDDA_3") (pintype "bidirectional"))
      (node (ref "U$9") (pin "4") (pinfunction "VDDD_4") (pintype "bidirectional"))
    )
    (net (code "60") (name "Net-(U$7-C1)") (class "Default")
      (node (ref "CA2") (pin "1") (pinfunction "1_1") (pintype "passive"))
      (node (ref "U$7") (pin "6") (pinfunction "C1_6") (pintype "bidirectional"))
    )
    (net (code "61") (name "Net-(U$7-SETC)") (class "Default")
      (node (ref "CA3") (pin "1") (pinfunction "1_1") (pintype "passive"))
      (node (ref "U$7") (pin "13") (pinfunction "SETC_13") (pintype "bidirectional"))
    )
    (net (code "62") (name "Net-(U$7-SETP)") (class "Default")
      (node (ref "CA3") (pin "2") (pinfunction "2_2") (pintype "passive"))
      (node (ref "U$7") (pin "12") (pinfunction "SETP_12") (pintype "bidirectional"))
    )
    (net (code "63") (name "Net-(U$12-P$2)") (class "Default")
      (node (ref "R5") (pin "1") (pinfunction "1_1") (pintype "passive"))
      (node (ref "U$12") (pin "2") (pinfunction "P$2_2") (pintype "bidirectional"))
    )
    (net (code "64") (name "Net-(U$12-P$3)") (class "Default")
      (node (ref "R4") (pin "1") (pinfunction "1_1") (pintype "passive"))
      (node (ref "U$12") (pin "3") (pinfunction "P$3_3") (pintype "bidirectional"))
    )
    (net (code "65") (name "PWM1") (class "Default")
      (node (ref "R9") (pin "1") (pinfunction "1_1") (pintype "passive"))
      (node (ref "U$1") (pin "P30") (pinfunction "PA11_P30") (pintype "bidirectional"))
    )
    (net (code "66") (name "PWM2") (class "Default")
      (node (ref "R11") (pin "1") (pinfunction "1_1") (pintype "passive"))
      (node (ref "U$1") (pin "P31") (pinfunction "PA12_P31") (pintype "bidirectional"))
    )
    (net (code "67") (name "PWM3") (class "Default")
      (node (ref "R13") (pin "1") (pinfunction "1_1") (pintype "passive"))
      (node (ref "U$1") (pin "P33") (pinfunction "PA13_P33") (pintype "bidirectional"))
    )
    (net (code "68") (name "PWM4") (class "Default")
      (node (ref "R15") (pin "1") (pinfunction "1_1") (pintype "passive"))
      (node (ref "U$1") (pin "P60") (pinfunction "PA25_P60") (pintype "bidirectional"))
    )
    (net (code "69") (name "PWM5") (class "Default")
      (node (ref "R17") (pin "1") (pinfunction "1_1") (pintype "passive"))
      (node (ref "U$1") (pin "P36") (pinfunction "PA16_P36") (pintype "bidirectional"))
    )
    (net (code "70") (name "PWM6") (class "Default")
      (node (ref "R19") (pin "1") (pinfunction "1_1") (pintype "passive"))
      (node (ref "U$1") (pin "P16") (pinfunction "PA31_P16") (pintype "bidirectional"))
    )
    (net (code "71") (name "RC1-RX1") (class "Default")
      (node (ref "R3") (pin "1") (pinfunction "1_1") (pintype "passive"))
      (node (ref "U$1") (pin "P25") (pinfunction "PB03_P25") (pintype "bidirectional"))
    )
    (net (code "72") (name "RC2") (class "Default")
      (node (ref "R6") (pin "1") (pinfunction "1_1") (pintype "passive"))
      (node (ref "U$1") (pin "P12") (pinfunction "PA06_P12") (pintype "bidirectional"))
    )
    (net (code "73") (name "RC3") (class "Default")
      (node (ref "R7") (pin "1") (pinfunction "1_1") (pintype "passive"))
      (node (ref "U$1") (pin "P34") (pinfunction "PA14_P34") (pintype "bidirectional"))
    )
    (net (code "74") (name "RC4") (class "Default")
      (node (ref "R8") (pin "1") (pinfunction "1_1") (pintype "passive"))
      (node (ref "U$1") (pin "P47") (pinfunction "PA23_P47") (pintype "bidirectional"))
    )
    (net (code "75") (name "RX_SW") (class "Default")
      (node (ref "T1") (pin "P$1") (pinfunction "G_P$1") (pintype "passive"))
      (node (ref "T1") (pin "P$3") (pinfunction "G_P$3") (pintype "passive"))
      (node (ref "U$1") (pin "P15") (pinfunction "PA30_P15") (pintype "bidirectional"))
    )
    (net (code "76") (name "SCK") (class "Default")
      (node (ref "U$1") (pin "P35") (pinfunction "PA15_P35") (pintype "bidirectional"))
      (node (ref "U$5") (pin "2") (pinfunction "SCL/SCK_2") (pintype "input"))
    )
    (net (code "77") (name "UART0_RX") (class "Default")
      (node (ref "U$1") (pin "P57") (pinfunction "PB10_P57") (pintype "bidirectional"))
      (node (ref "U$11") (pin "3") (pinfunction "P$3_3") (pintype "bidirectional"))
    )
    (net (code "78") (name "UART0_TX") (class "Default")
      (node (ref "U$1") (pin "P58") (pinfunction "PB11_P58") (pintype "bidirectional"))
      (node (ref "U$11") (pin "2") (pinfunction "P$2_2") (pintype "bidirectional"))
    )
    (net (code "79") (name "UART2_RX") (class "Default")
      (node (ref "U$1") (pin "P62") (pinfunction "PA27_P62") (pintype "bidirectional"))
      (node (ref "U$10") (pin "2") (pinfunction "P$2_2") (pintype "bidirectional"))
    )
    (net (code "80") (name "UART2_TX") (class "Default")
      (node (ref "U$1") (pin "P61") (pinfunction "PA26_P61") (pintype "bidirectional"))
      (node (ref "U$10") (pin "3") (pinfunction "P$3_3") (pintype "bidirectional"))
    )
    (net (code "81") (name "unconnected-(U$1-PA03-PadP9)") (class "Default")
      (node (ref "U$1") (pin "P9") (pinfunction "PA03_P9") (pintype "bidirectional"))
    )
    (net (code "82") (name "unconnected-(U$1-PA04-PadP10)") (class "Default")
      (node (ref "U$1") (pin "P10") (pinfunction "PA04_P10") (pintype "bidirectional"))
    )
    (net (code "83") (name "unconnected-(U$1-PA07-PadP13)") (class "Default")
      (node (ref "U$1") (pin "P13") (pinfunction "PA07_P13") (pintype "bidirectional"))
    )
    (net (code "84") (name "unconnected-(U$1-PA08-PadP14)") (class "Default")
      (node (ref "U$1") (pin "P14") (pinfunction "PA08_P14") (pintype "bidirectional"))
    )
    (net (code "85") (name "unconnected-(U$1-PA17-PadP37)") (class "Default")
      (node (ref "U$1") (pin "P37") (pinfunction "PA17_P37") (pintype "bidirectional"))
    )
    (net (code "86") (name "unconnected-(U$1-PB04-PadP26)") (class "Default")
      (node (ref "U$1") (pin "P26") (pinfunction "PB04_P26") (pintype "bidirectional"))
    )
    (net (code "87") (name "unconnected-(U$1-PB05-PadP27)") (class "Default")
      (node (ref "U$1") (pin "P27") (pinfunction "PB05_P27") (pintype "bidirectional"))
    )
    (net (code "88") (name "unconnected-(U$1-PB06-PadP38)") (class "Default")
      (node (ref "U$1") (pin "P38") (pinfunction "PB06_P38") (pintype "bidirectional"))
    )
    (net (code "89") (name "unconnected-(U$1-PB07-PadP43)") (class "Default")
      (node (ref "U$1") (pin "P43") (pinfunction "PB07_P43") (pintype "bidirectional"))
    )
    (net (code "90") (name "unconnected-(U$1-PB08-PadP54)") (class "Default")
      (node (ref "U$1") (pin "P54") (pinfunction "PB08_P54") (pintype "bidirectional"))
    )
    (net (code "91") (name "unconnected-(U$1-PB09-PadP55)") (class "Default")
      (node (ref "U$1") (pin "P55") (pinfunction "PB09_P55") (pintype "bidirectional"))
    )
    (net (code "92") (name "unconnected-(U$4-ID-PadP$4)") (class "Default")
      (node (ref "U$4") (pin "P$4") (pinfunction "ID_P$4") (pintype "bidirectional"))
    )
    (net (code "93") (name "unconnected-(U$5-INT1-Pad7)") (class "Default")
      (node (ref "U$5") (pin "7") (pinfunction "INT1_7") (pintype "input"))
    )
    (net (code "94") (name "unconnected-(U$7-DRDY-Pad9)") (class "Default")
      (node (ref "U$7") (pin "9") (pinfunction "DRDY_9") (pintype "bidirectional"))
    )
    (net (code "95") (name "unconnected-(U$7-INT2-Pad4)") (class "Default")
      (node (ref "U$7") (pin "4") (pinfunction "INT2_4") (pintype "bidirectional"))
    )
    (net (code "96") (name "unconnected-(U$7-NC-Pad8)") (class "Default")
      (node (ref "U$7") (pin "8") (pinfunction "NC_8") (pintype "bidirectional"))
    )
    (net (code "97") (name "unconnected-(U$9-EOC-Pad2)") (class "Default")
      (node (ref "U$9") (pin "2") (pinfunction "EOC_2") (pintype "bidirectional"))
    )
    (net (code "98") (name "unconnected-(U$9-NC-Pad5)") (class "Default")
      (node (ref "U$9") (pin "5") (pinfunction "NC_5") (pintype "bidirectional"))
    )
    (net (code "99") (name "unconnected-(U$9-XCLR-Pad8)") (class "Default")
      (node (ref "U$9") (pin "8") (pinfunction "XCLR_8") (pintype "bidirectional"))
    )
  )
)
